# Power.net
KiCad netlist of a schematic drawn in Altium Designer
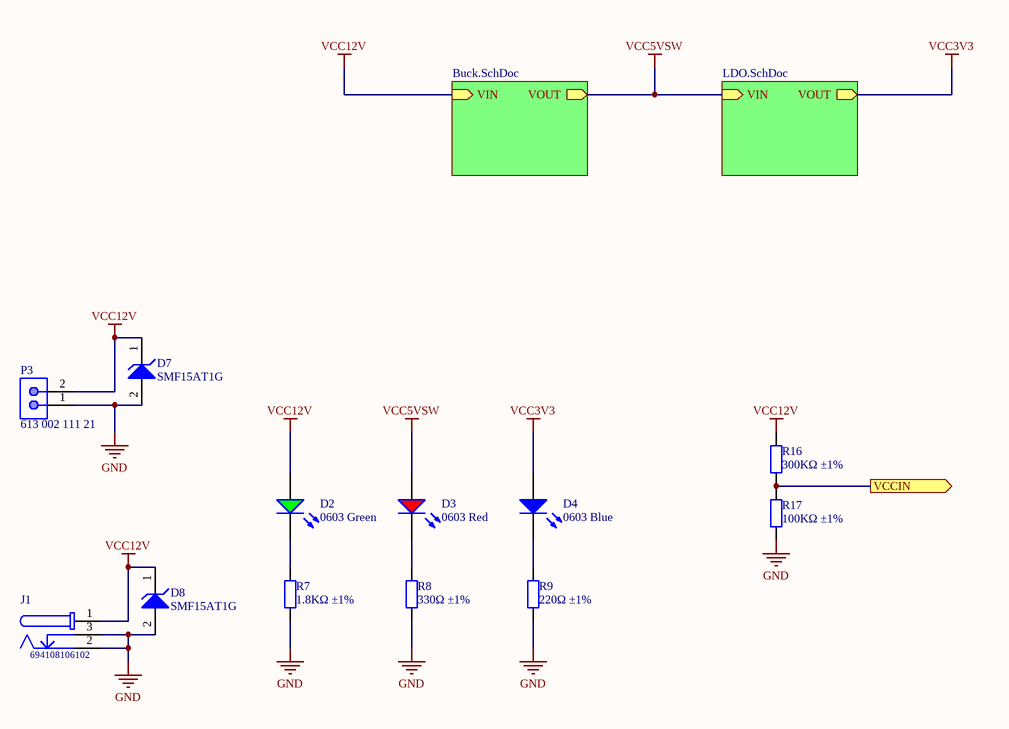
[diagram p0: Power.SchDoc]

(export (version "E")
  (design (tool "Eeschema 10.0.6"))
  (components
    (comp (ref "D2")
      (value "0603 Green")
      (footprint "0603_LED_S1")
      (description "LED")
      (libsource (lib "Miscellaneous Devices LC") (part "0603 LED Green"))
    )
    (comp (ref "D3")
      (value "0603 Red")
      (footprint "0603_LED_S1")
      (description "LED")
      (libsource (lib "Miscellaneous Devices LC") (part "0603 LED Red"))
    )
    (comp (ref "D4")
      (value "0603 Blue")
      (footprint "0603_LED_S1")
      (description "LED")
      (libsource (lib "Miscellaneous Devices LC") (part "0603 LED Blue"))
    )
    (comp (ref "D7")
      (value "SMF15AT1G")
      (footprint "ONSC-SOD-123FL-2-498_V")
      (description "200 W Transient Voltage Suppressor, 2-Pin SOD-123FL, Pb-Free, Tape and Reel")
      (fields (field (name "MANUFACTURER") "On Semiconductor"))
      (libsource (lib "Altium Content Vault") (part "ONSC-K1A2-2"))
    )
    (comp (ref "D8")
      (value "SMF15AT1G")
      (footprint "ONSC-SOD-123FL-2-498_V")
      (description "200 W Transient Voltage Suppressor, 2-Pin SOD-123FL, Pb-Free, Tape and Reel")
      (fields (field (name "MANUFACTURER") "On Semiconductor"))
      (libsource (lib "Altium Content Vault") (part "ONSC-K1A2-2"))
    )
    (comp (ref "J1")
      (value "694108106102")
      (footprint "694108106102")
      (description "DC Power Jack Connector with 4 soldering pads & Pegs WR-DC, Male, Right Angled, SMT, 5 A, 24 V")
      (fields (field (name "MANUFACTURER") "Wurth Elektronik") (field (name "PUBLISHER") "WurthElektronik"))
      (libsource (lib "Altium Content Vault") (part "WE-JACK-2CD3-RN"))
    )
    (comp (ref "P3")
      (value "613 002 111 21")
      (footprint "WE-61300211121_V")
      (libsource (lib "Altium Content Vault") (part "CN-1P-M-R2"))
    )
    (comp (ref "R7")
      (value "1.8KΩ ±1%")
      (footprint "0603_R")
      (description "Chip resistor")
      (fields (field (name "MANUFACTURER") "Uniroyal Elec") (field (name "PARTNUMBER") "0603WAF1801T5E"))
      (libsource (lib "Miscellaneous Devices LC") (part "0603 1.8K (1801) 1%"))
    )
    (comp (ref "R8")
      (value "330Ω ±1%")
      (footprint "0603_R")
      (description "Chip resistor")
      (fields (field (name "MANUFACTURER") "Uniroyal Elec") (field (name "PARTNUMBER") "0603WAF3300T5E"))
      (libsource (lib "Miscellaneous Devices LC") (part "0603 330R (3300) 1%"))
    )
    (comp (ref "R9")
      (value "220Ω ±1%")
      (footprint "0603_R")
      (description "Chip resistor")
      (fields (field (name "MANUFACTURER") "Uniroyal Elec") (field (name "PARTNUMBER") "0603WAF2200T5E"))
      (libsource (lib "Miscellaneous Devices LC") (part "0603 220R (2200) 1%"))
    )
    (comp (ref "R16")
      (value "300KΩ ±1%")
      (footprint "0402_R")
      (description "Chip resistor")
      (fields (field (name "MANUFACTURER") "Uniroyal Elec") (field (name "PARTNUMBER") "0402WGF3003TCE"))
      (libsource (lib "Miscellaneous Devices LC") (part "0402 300K (3003) 1%"))
    )
    (comp (ref "R17")
      (value "100KΩ ±1%")
      (footprint "0402_R")
      (description "Chip resistor")
      (fields (field (name "MANUFACTURER") "Uniroyal Elec") (field (name "PARTNUMBER") "0402WGF1003TCE"))
      (libsource (lib "Miscellaneous Devices LC") (part "0402 100K (1003) 1%"))
    )
  )
  (nets
    (net (code "1") (name "/VCCIN") (class "Default")
      (node (ref "R16") (pin "1") (pinfunction "1_1") (pintype "passive"))
      (node (ref "R17") (pin "2") (pinfunction "2_2") (pintype "passive"))
    )
    (net (code "2") (name "GND") (class "Default")
      (node (ref "D7") (pin "2") (pinfunction "A_2") (pintype "passive"))
      (node (ref "D8") (pin "2") (pinfunction "A_2") (pintype "passive"))
      (node (ref "J1") (pin "2") (pinfunction "2_2") (pintype "passive"))
      (node (ref "J1") (pin "3") (pinfunction "3_3") (pintype "passive"))
      (node (ref "P3") (pin "1") (pinfunction "1_1") (pintype "passive"))
      (node (ref "R17") (pin "1") (pinfunction "1_1") (pintype "passive"))
      (node (ref "R7") (pin "1") (pinfunction "1_1") (pintype "passive"))
      (node (ref "R8") (pin "1") (pinfunction "1_1") (pintype "passive"))
      (node (ref "R9") (pin "1") (pinfunction "1_1") (pintype "passive"))
    )
    (net (code "3") (name "Net-(D2-PadK)") (class "Default")
      (node (ref "D2") (pin "K") (pinfunction "K_K") (pintype "passive"))
      (node (ref "R7") (pin "2") (pinfunction "2_2") (pintype "passive"))
    )
    (net (code "4") (name "Net-(D3-PadK)") (class "Default")
      (node (ref "D3") (pin "K") (pinfunction "K_K") (pintype "passive"))
      (node (ref "R8") (pin "2") (pinfunction "2_2") (pintype "passive"))
    )
    (net (code "5") (name "Net-(D4-PadK)") (class "Default")
      (node (ref "D4") (pin "K") (pinfunction "K_K") (pintype "passive"))
      (node (ref "R9") (pin "2") (pinfunction "2_2") (pintype "passive"))
    )
    (net (code "6") (name "VCC3V3") (class "Default")
      (node (ref "D4") (pin "A") (pinfunction "A_A") (pintype "passive"))
    )
    (net (code "7") (name "VCC5VSW") (class "Default")
      (node (ref "D3") (pin "A") (pinfunction "A_A") (pintype "passive"))
    )
    (net (code "8") (name "VCC12V") (class "Default")
      (node (ref "D2") (pin "A") (pinfunction "A_A") (pintype "passive"))
      (node (ref "D7") (pin "1") (pinfunction "K_1") (pintype "passive"))
      (node (ref "D8") (pin "1") (pinfunction "K_1") (pintype "passive"))
      (node (ref "J1") (pin "1") (pinfunction "1_1") (pintype "passive"))
      (node (ref "P3") (pin "2") (pinfunction "2_2") (pintype "passive"))
      (node (ref "R16") (pin "2") (pinfunction "2_2") (pintype "passive"))
    )
  )
)
